# measure_station.net
KiCad netlist of a schematic drawn in EAGLE
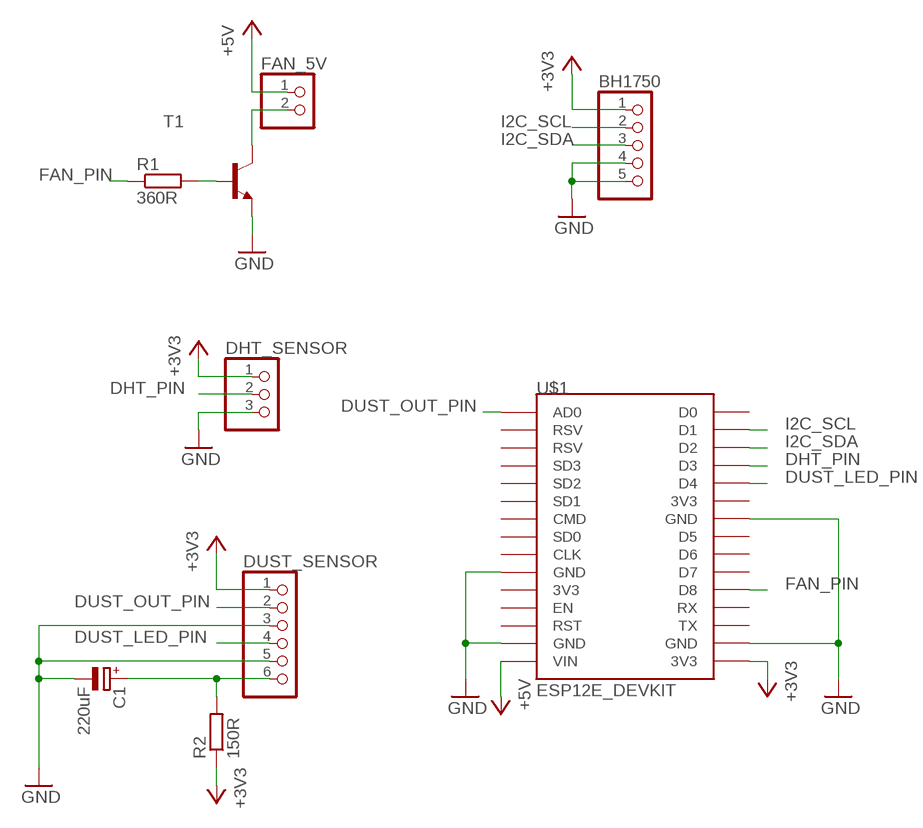
[diagram p0: schematic, sheet 1]

(export (version "E")
  (design (tool "Eeschema 10.0.6"))
  (components
    (comp (ref "BH1750")
      (value "PINHD-1X5")
      (footprint "eagle-import:1X05")
      (libsource (lib "eagle-import") (part "PINHD-1X5"))
    )
    (comp (ref "C1")
      (value "220uF")
      (footprint "eagle-import:E2,5-5")
      (libsource (lib "eagle-import") (part "CPOL-EUE2.5-5"))
    )
    (comp (ref "DHT_SENSOR")
      (value "PINHD-1X3")
      (footprint "eagle-import:1X03")
      (libsource (lib "eagle-import") (part "PINHD-1X3"))
    )
    (comp (ref "DUST_SENSOR")
      (value "PINHD-1X6")
      (footprint "eagle-import:1X06")
      (libsource (lib "eagle-import") (part "PINHD-1X6"))
    )
    (comp (ref "FAN_5V")
      (value "PINHD-1X2")
      (footprint "eagle-import:1X02")
      (libsource (lib "eagle-import") (part "PINHD-1X2"))
    )
    (comp (ref "R1")
      (value "360R")
      (footprint "eagle-import:0204_7")
      (libsource (lib "eagle-import") (part "R-EU_0204/7"))
    )
    (comp (ref "R2")
      (value "150R")
      (footprint "eagle-import:0204_7")
      (libsource (lib "eagle-import") (part "R-EU_0204/7"))
    )
    (comp (ref "T1")
      (value "MPS2222A-NPN-TO92-CBE")
      (footprint "eagle-import:TO92-CBE")
      (libsource (lib "eagle-import") (part "-NPN-TO92-CBEMPS2222A"))
    )
    (comp (ref "U$1")
      (value "ESP12E_DEVKIT")
      (footprint "eagle-import:ESP12E_DEVKIT")
      (libsource (lib "eagle-import") (part "ESP12E_DEVKIT"))
    )
  )
  (nets
    (net (code "1") (name "+3V3") (class "Default")
      (node (ref "BH1750") (pin "1") (pinfunction "1_1") (pintype "passive"))
      (node (ref "DHT_SENSOR") (pin "1") (pinfunction "1_1") (pintype "passive"))
      (node (ref "DUST_SENSOR") (pin "1") (pinfunction "1_1") (pintype "passive"))
      (node (ref "R2") (pin "1") (pinfunction "1_1") (pintype "passive"))
      (node (ref "U$1") (pin "3V3@2") (pinfunction "3V3_3V3@2") (pintype "bidirectional"))
    )
    (net (code "2") (name "+5V") (class "Default")
      (node (ref "FAN_5V") (pin "1") (pinfunction "1_1") (pintype "passive"))
      (node (ref "U$1") (pin "VIN") (pinfunction "VIN_VIN") (pintype "bidirectional"))
    )
    (net (code "3") (name "/DHT_PIN") (class "Default")
      (node (ref "DHT_SENSOR") (pin "2") (pinfunction "2_2") (pintype "passive"))
      (node (ref "U$1") (pin "D3") (pinfunction "D3_D3") (pintype "bidirectional"))
    )
    (net (code "4") (name "/DUST_LED_PIN") (class "Default")
      (node (ref "DUST_SENSOR") (pin "4") (pinfunction "4_4") (pintype "passive"))
      (node (ref "U$1") (pin "D4") (pinfunction "D4_D4") (pintype "bidirectional"))
    )
    (net (code "5") (name "/DUST_OUT_PIN") (class "Default")
      (node (ref "DUST_SENSOR") (pin "2") (pinfunction "2_2") (pintype "passive"))
      (node (ref "U$1") (pin "AD0") (pinfunction "AD0_AD0") (pintype "bidirectional"))
    )
    (net (code "6") (name "/FAN_PIN") (class "Default")
      (node (ref "R1") (pin "1") (pinfunction "1_1") (pintype "passive"))
      (node (ref "U$1") (pin "D8") (pinfunction "D8_D8") (pintype "bidirectional"))
    )
    (net (code "7") (name "/I2C_SCL") (class "Default")
      (node (ref "BH1750") (pin "2") (pinfunction "2_2") (pintype "passive"))
      (node (ref "U$1") (pin "D1") (pinfunction "D1_D1") (pintype "bidirectional"))
    )
    (net (code "8") (name "/I2C_SDA") (class "Default")
      (node (ref "BH1750") (pin "3") (pinfunction "3_3") (pintype "passive"))
      (node (ref "U$1") (pin "D2") (pinfunction "D2_D2") (pintype "bidirectional"))
    )
    (net (code "9") (name "GND") (class "Default")
      (node (ref "BH1750") (pin "4") (pinfunction "4_4") (pintype "passive"))
      (node (ref "BH1750") (pin "5") (pinfunction "5_5") (pintype "passive"))
      (node (ref "C1") (pin "-") (pinfunction "-_-") (pintype "passive"))
      (node (ref "DHT_SENSOR") (pin "3") (pinfunction "3_3") (pintype "passive"))
      (node (ref "DUST_SENSOR") (pin "3") (pinfunction "3_3") (pintype "passive"))
      (node (ref "DUST_SENSOR") (pin "5") (pinfunction "5_5") (pintype "passive"))
      (node (ref "T1") (pin "E") (pinfunction "E_E") (pintype "passive"))
      (node (ref "U$1") (pin "GND@0") (pinfunction "GND_GND@0") (pintype "bidirectional"))
      (node (ref "U$1") (pin "GND@1") (pinfunction "GND_GND@1") (pintype "bidirectional"))
      (node (ref "U$1") (pin "GND@2") (pinfunction "GND_GND@2") (pintype "bidirectional"))
      (node (ref "U$1") (pin "GND@3") (pinfunction "GND_GND@3") (pintype "bidirectional"))
    )
    (net (code "10") (name "Net-(C1-Pad+)") (class "Default")
      (node (ref "C1") (pin "+") (pinfunction "+_+") (pintype "passive"))
      (node (ref "DUST_SENSOR") (pin "6") (pinfunction "6_6") (pintype "passive"))
      (node (ref "R2") (pin "2") (pinfunction "2_2") (pintype "passive"))
    )
    (net (code "11") (name "Net-(FAN_5V-Pad2)") (class "Default")
      (node (ref "FAN_5V") (pin "2") (pinfunction "2_2") (pintype "passive"))
      (node (ref "T1") (pin "C") (pinfunction "C_C") (pintype "passive"))
    )
    (net (code "12") (name "Net-(R1-Pad2)") (class "Default")
      (node (ref "R1") (pin "2") (pinfunction "2_2") (pintype "passive"))
      (node (ref "T1") (pin "B") (pinfunction "B_B") (pintype "passive"))
    )
    (net (code "13") (name "unconnected-(U$1-3V3-Pad3V3@0)") (class "Default")
      (node (ref "U$1") (pin "3V3@0") (pinfunction "3V3_3V3@0") (pintype "bidirectional"))
    )
    (net (code "14") (name "unconnected-(U$1-3V3-Pad3V3@1)") (class "Default")
      (node (ref "U$1") (pin "3V3@1") (pinfunction "3V3_3V3@1") (pintype "bidirectional"))
    )
    (net (code "15") (name "unconnected-(U$1-PadCLK)") (class "Default")
      (node (ref "U$1") (pin "CLK") (pinfunction "CLK_CLK") (pintype "bidirectional"))
    )
    (net (code "16") (name "unconnected-(U$1-PadCMD)") (class "Default")
      (node (ref "U$1") (pin "CMD") (pinfunction "CMD_CMD") (pintype "bidirectional"))
    )
    (net (code "17") (name "unconnected-(U$1-PadD0)") (class "Default")
      (node (ref "U$1") (pin "D0") (pinfunction "D0_D0") (pintype "bidirectional"))
    )
    (net (code "18") (name "unconnected-(U$1-PadD5)") (class "Default")
      (node (ref "U$1") (pin "D5") (pinfunction "D5_D5") (pintype "bidirectional"))
    )
    (net (code "19") (name "unconnected-(U$1-PadD6)") (class "Default")
      (node (ref "U$1") (pin "D6") (pinfunction "D6_D6") (pintype "bidirectional"))
    )
    (net (code "20") (name "unconnected-(U$1-PadD7)") (class "Default")
      (node (ref "U$1") (pin "D7") (pinfunction "D7_D7") (pintype "bidirectional"))
    )
    (net (code "21") (name "unconnected-(U$1-PadEN)") (class "Default")
      (node (ref "U$1") (pin "EN") (pinfunction "EN_EN") (pintype "bidirectional"))
    )
    (net (code "22") (name "unconnected-(U$1-PadRST)") (class "Default")
      (node (ref "U$1") (pin "RST") (pinfunction "RST_RST") (pintype "bidirectional"))
    )
    (net (code "23") (name "unconnected-(U$1-PadRX)") (class "Default")
      (node (ref "U$1") (pin "RX") (pinfunction "RX_RX") (pintype "bidirectional"))
    )
    (net (code "24") (name "unconnected-(U$1-PadSD0)") (class "Default")
      (node (ref "U$1") (pin "SD0") (pinfunction "SD0_SD0") (pintype "bidirectional"))
    )
    (net (code "25") (name "unconnected-(U$1-PadSD1)") (class "Default")
      (node (ref "U$1") (pin "SD1") (pinfunction "SD1_SD1") (pintype "bidirectional"))
    )
    (net (code "26") (name "unconnected-(U$1-PadSD2)") (class "Default")
      (node (ref "U$1") (pin "SD2") (pinfunction "SD2_SD2") (pintype "bidirectional"))
    )
    (net (code "27") (name "unconnected-(U$1-PadSD3)") (class "Default")
      (node (ref "U$1") (pin "SD3") (pinfunction "SD3_SD3") (pintype "bidirectional"))
    )
    (net (code "28") (name "unconnected-(U$1-PadTX)") (class "Default")
      (node (ref "U$1") (pin "TX") (pinfunction "TX_TX") (pintype "bidirectional"))
    )
    (net (code "29") (name "unconnected-(U$1-RSV-PadRSV@0)") (class "Default")
      (node (ref "U$1") (pin "RSV@0") (pinfunction "RSV_RSV@0") (pintype "bidirectional"))
    )
    (net (code "30") (name "unconnected-(U$1-RSV-PadRSV@1)") (class "Default")
      (node (ref "U$1") (pin "RSV@1") (pinfunction "RSV_RSV@1") (pintype "bidirectional"))
    )
  )
)
